# mcu.net
KiCad netlist of a schematic drawn in Altium Designer
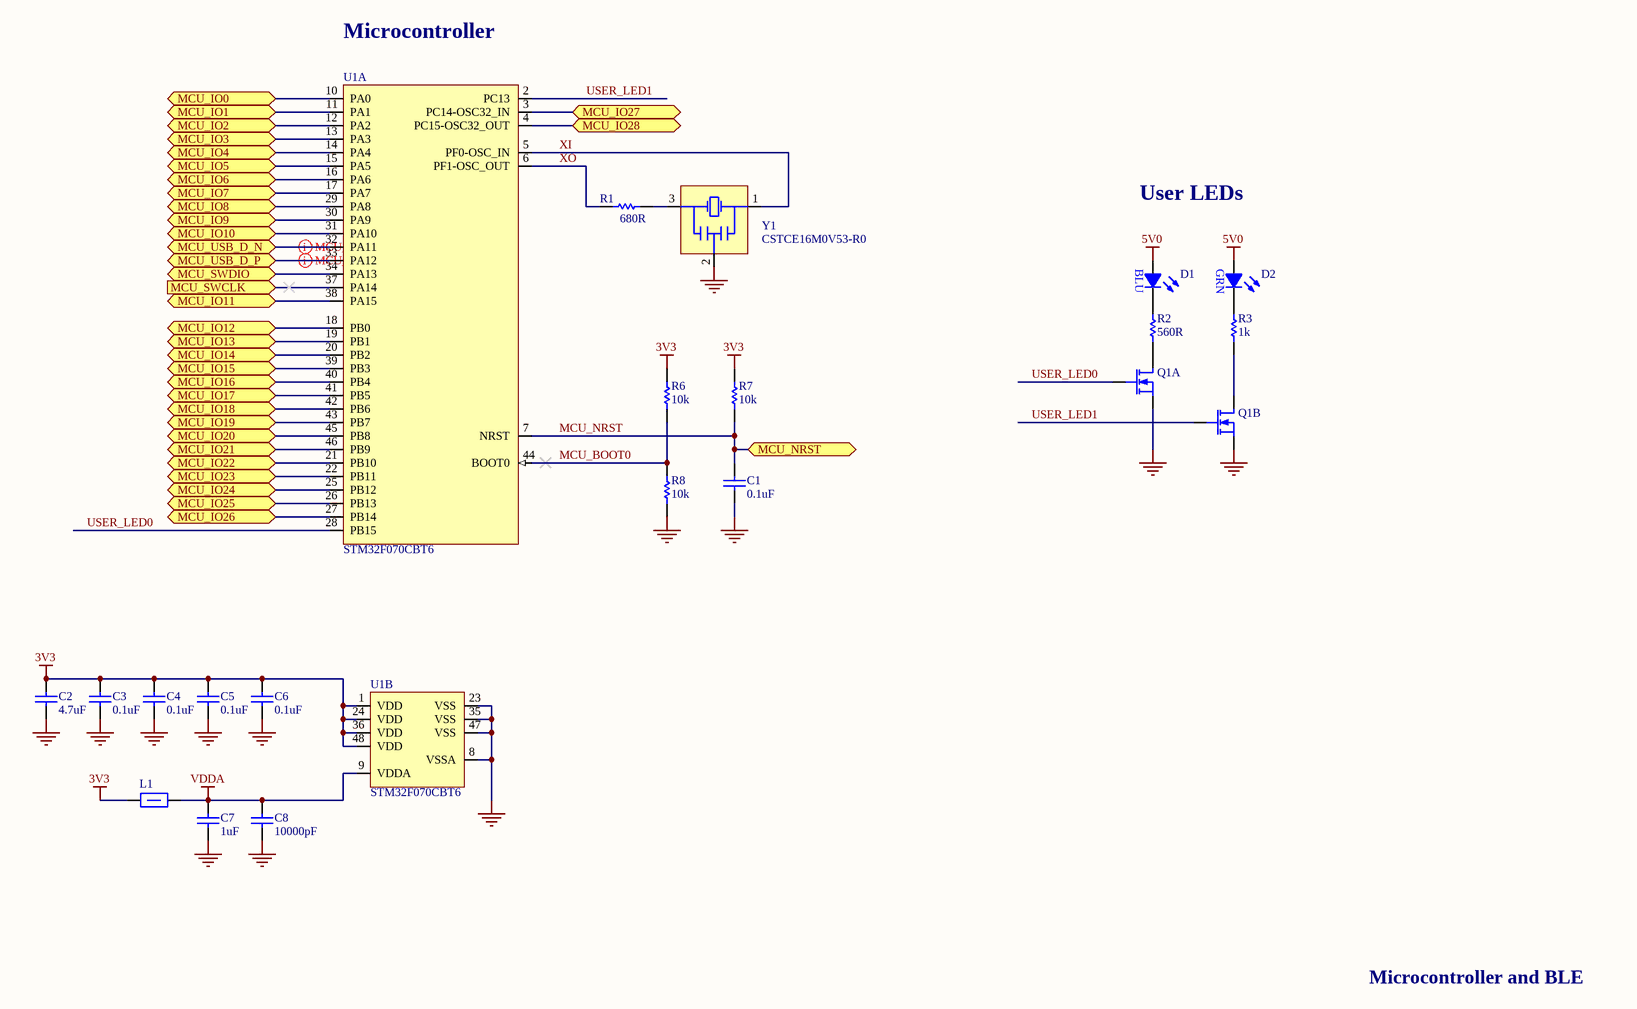
[diagram p0: mcu.SchDoc]

(export (version "E")
  (design (tool "Eeschema 10.0.6"))
  (components
    (comp (ref "C1")
      (value "0.1uF")
      (footprint "C0201")
      (description "CAP CER 0.1UF 16V X5R 0201")
      (fields
        (field (name "MANUFACTURER") "Murata")
        (field (name "MANUFACTURER PART NUMBER") "GRM033R61C104ME84D")
      )
      (libsource (lib "Capacitors") (part "0.1uF 16V 0201"))
    )
    (comp (ref "C2")
      (value "4.7uF")
      (footprint "C0402")
      (description "CAP CER 4.7UF 16V X5R 0402")
      (fields
        (field (name "MANUFACTURER") "Samsung")
        (field (name "MANUFACTURER PART NUMBER") "CL05A475MO5NUNC")
      )
      (libsource (lib "Capacitors") (part "4.7uF 16V 0402"))
    )
    (comp (ref "C3")
      (value "0.1uF")
      (footprint "C0201")
      (description "CAP CER 0.1UF 16V X5R 0201")
      (fields
        (field (name "MANUFACTURER") "Murata")
        (field (name "MANUFACTURER PART NUMBER") "GRM033R61C104ME84D")
      )
      (libsource (lib "Capacitors") (part "0.1uF 16V 0201"))
    )
    (comp (ref "C4")
      (value "0.1uF")
      (footprint "C0201")
      (description "CAP CER 0.1UF 16V X5R 0201")
      (fields
        (field (name "MANUFACTURER") "Murata")
        (field (name "MANUFACTURER PART NUMBER") "GRM033R61C104ME84D")
      )
      (libsource (lib "Capacitors") (part "0.1uF 16V 0201"))
    )
    (comp (ref "C5")
      (value "0.1uF")
      (footprint "C0201")
      (description "CAP CER 0.1UF 16V X5R 0201")
      (fields
        (field (name "MANUFACTURER") "Murata")
        (field (name "MANUFACTURER PART NUMBER") "GRM033R61C104ME84D")
      )
      (libsource (lib "Capacitors") (part "0.1uF 16V 0201"))
    )
    (comp (ref "C6")
      (value "0.1uF")
      (footprint "C0201")
      (description "CAP CER 0.1UF 16V X5R 0201")
      (fields
        (field (name "MANUFACTURER") "Murata")
        (field (name "MANUFACTURER PART NUMBER") "GRM033R61C104ME84D")
      )
      (libsource (lib "Capacitors") (part "0.1uF 16V 0201"))
    )
    (comp (ref "C7")
      (value "1uF")
      (footprint "C0402")
      (description "CAP CER 1UF 25V X5R 0402")
      (fields
        (field (name "MANUFACTURER") "Taiyo Yuden")
        (field (name "MANUFACTURER PART NUMBER") "TMK105BJ105MV-F")
      )
      (libsource (lib "Capacitors") (part "1uF 25V 0402"))
    )
    (comp (ref "C8")
      (value "10000pF")
      (footprint "C0201")
      (description "CAP CER 10000PF 25V X5R 0201")
      (fields
        (field (name "MANUFACTURER") "Murata")
        (field (name "MANUFACTURER PART NUMBER") "GRM033R61E103MA12D")
      )
      (libsource (lib "Capacitors") (part "10000pF 25V 0201"))
    )
    (comp (ref "D1")
      (value "5988091107F")
      (footprint "LED0603")
      (description "LED BLUE CLEAR 0603 SMD")
      (fields
        (field (name "MANUFACTURER") "Dialight")
        (field (name "MANUFACTURER PART NUMBER") "598-8091-107F")
      )
      (libsource (lib "Diodes") (part "Blue 0603 LED"))
    )
    (comp (ref "D2")
      (value "5988070107F")
      (footprint "LED0603")
      (description "LED GREEN CLEAR 0603 SMD")
      (fields
        (field (name "MANUFACTURER") "Dialight")
        (field (name "MANUFACTURER PART NUMBER") "598-8070-107F")
      )
      (libsource (lib "Diodes") (part "Green 0603 LED"))
    )
    (comp (ref "L1")
      (value "BLM15AG601SN1D")
      (footprint "L0402")
      (description "FERRITE BEAD 600 OHM 0402 1LN")
      (fields (field (name "MANUFACTURER") "Murata") (field (name "TOLERANCE") "25%"))
      (libsource (lib "Inductors") (part "BLM15AG601SN1D"))
    )
    (comp (ref "Q1")
      (value "PMDXB600UNE")
      (footprint "NXP_DFN1010B-6")
      (description "MOSFET 2N-CH 20V 0.6A 6DFN")
      (fields (field (name "MANUFACTURER") "NXP Semiconductors"))
      (libsource (lib "ICs") (part "PMDXB600UNE"))
    )
    (comp (ref "R1")
      (value "680R")
      (footprint "R0201")
      (description "RES SMD 680 OHM 1% 1/20W 0201")
      (fields
        (field (name "MANUFACTURER") "Yageo")
        (field (name "MANUFACTURER PART NUMBER") "RC0201FR-07680RL")
      )
      (libsource (lib "Resistors") (part "680R 0201"))
    )
    (comp (ref "R2")
      (value "560R")
      (footprint "R0201")
      (description "RES SMD 560 OHM 1% 1/20W 0201")
      (fields
        (field (name "MANUFACTURER") "Panasonic ECG")
        (field (name "MANUFACTURER PART NUMBER") "ERJ-1GEF5600C")
      )
      (libsource (lib "Resistors") (part "560R 0201"))
    )
    (comp (ref "R3")
      (value "1k")
      (footprint "R0201")
      (description "RES SMD 1K OHM 1% 1/20W 0201")
      (fields
        (field (name "MANUFACTURER") "Panasonic ECG")
        (field (name "MANUFACTURER PART NUMBER") "ERJ-1GEF1001C")
      )
      (libsource (lib "Resistors") (part "1k 0201"))
    )
    (comp (ref "R6")
      (value "10k")
      (footprint "R0201")
      (description "RES SMD 10K OHM 1% 1/20W 0201")
      (fields
        (field (name "MANUFACTURER") "Panasonic ECG")
        (field (name "MANUFACTURER PART NUMBER") "ERJ-1GEF1002C")
      )
      (libsource (lib "Resistors") (part "10k 0201"))
    )
    (comp (ref "R7")
      (value "10k")
      (footprint "R0201")
      (description "RES SMD 10K OHM 1% 1/20W 0201")
      (fields
        (field (name "MANUFACTURER") "Panasonic ECG")
        (field (name "MANUFACTURER PART NUMBER") "ERJ-1GEF1002C")
      )
      (libsource (lib "Resistors") (part "10k 0201"))
    )
    (comp (ref "R8")
      (value "10k")
      (footprint "R0201")
      (description "RES SMD 10K OHM 1% 1/20W 0201")
      (fields
        (field (name "MANUFACTURER") "Panasonic ECG")
        (field (name "MANUFACTURER PART NUMBER") "ERJ-1GEF1002C")
      )
      (libsource (lib "Resistors") (part "10k 0201"))
    )
    (comp (ref "U1")
      (value "STM32F070CBT6")
      (footprint "STM_LQFP48")
      (description "IC MCU 32BIT 128KB FLASH 48LQFP")
      (fields (field (name "MANUFACTURER") "STMicroelectronics"))
      (libsource (lib "") (part "STM32F070CBT6_1"))
    )
    (comp (ref "Y1")
      (value "CSTCE16M0V53-R0")
      (footprint "MUR_CSTCE_V")
      (description "CER RES 16.0000MHZ 15PF SMD")
      (fields (field (name "MANUFACTURER") "Murata") (field (name "TOLERANCE") "0.5%"))
      (libsource (lib "Oscillators") (part "16MHz Resonator"))
    )
  )
  (nets
    (net (code "1") (name "/MCU_BOOT0") (class "Default")
      (node (ref "R6") (pin "1") (pinfunction "1_1") (pintype "passive"))
      (node (ref "R8") (pin "2") (pinfunction "2_2") (pintype "passive"))
      (node (ref "U1") (pin "44") (pinfunction "BOOT0_44") (pintype "input"))
    )
    (net (code "2") (name "/MCU_IO0") (class "Default")
      (node (ref "U1") (pin "10") (pinfunction "PA0_10") (pintype "bidirectional"))
    )
    (net (code "3") (name "/MCU_IO1") (class "Default")
      (node (ref "U1") (pin "11") (pinfunction "PA1_11") (pintype "bidirectional"))
    )
    (net (code "4") (name "/MCU_IO2") (class "Default")
      (node (ref "U1") (pin "12") (pinfunction "PA2_12") (pintype "bidirectional"))
    )
    (net (code "5") (name "/MCU_IO3") (class "Default")
      (node (ref "U1") (pin "13") (pinfunction "PA3_13") (pintype "bidirectional"))
    )
    (net (code "6") (name "/MCU_IO4") (class "Default")
      (node (ref "U1") (pin "14") (pinfunction "PA4_14") (pintype "bidirectional"))
    )
    (net (code "7") (name "/MCU_IO5") (class "Default")
      (node (ref "U1") (pin "15") (pinfunction "PA5_15") (pintype "bidirectional"))
    )
    (net (code "8") (name "/MCU_IO6") (class "Default")
      (node (ref "U1") (pin "16") (pinfunction "PA6_16") (pintype "bidirectional"))
    )
    (net (code "9") (name "/MCU_IO7") (class "Default")
      (node (ref "U1") (pin "17") (pinfunction "PA7_17") (pintype "bidirectional"))
    )
    (net (code "10") (name "/MCU_IO8") (class "Default")
      (node (ref "U1") (pin "29") (pinfunction "PA8_29") (pintype "bidirectional"))
    )
    (net (code "11") (name "/MCU_IO9") (class "Default")
      (node (ref "U1") (pin "30") (pinfunction "PA9_30") (pintype "bidirectional"))
    )
    (net (code "12") (name "/MCU_IO10") (class "Default")
      (node (ref "U1") (pin "31") (pinfunction "PA10_31") (pintype "bidirectional"))
    )
    (net (code "13") (name "/MCU_IO11") (class "Default")
      (node (ref "U1") (pin "38") (pinfunction "PA15_38") (pintype "bidirectional"))
    )
    (net (code "14") (name "/MCU_IO12") (class "Default")
      (node (ref "U1") (pin "18") (pinfunction "PB0_18") (pintype "bidirectional"))
    )
    (net (code "15") (name "/MCU_IO13") (class "Default")
      (node (ref "U1") (pin "19") (pinfunction "PB1_19") (pintype "bidirectional"))
    )
    (net (code "16") (name "/MCU_IO14") (class "Default")
      (node (ref "U1") (pin "20") (pinfunction "PB2_20") (pintype "bidirectional"))
    )
    (net (code "17") (name "/MCU_IO15") (class "Default")
      (node (ref "U1") (pin "39") (pinfunction "PB3_39") (pintype "bidirectional"))
    )
    (net (code "18") (name "/MCU_IO16") (class "Default")
      (node (ref "U1") (pin "40") (pinfunction "PB4_40") (pintype "bidirectional"))
    )
    (net (code "19") (name "/MCU_IO17") (class "Default")
      (node (ref "U1") (pin "41") (pinfunction "PB5_41") (pintype "bidirectional"))
    )
    (net (code "20") (name "/MCU_IO18") (class "Default")
      (node (ref "U1") (pin "42") (pinfunction "PB6_42") (pintype "bidirectional"))
    )
    (net (code "21") (name "/MCU_IO19") (class "Default")
      (node (ref "U1") (pin "43") (pinfunction "PB7_43") (pintype "bidirectional"))
    )
    (net (code "22") (name "/MCU_IO20") (class "Default")
      (node (ref "U1") (pin "45") (pinfunction "PB8_45") (pintype "bidirectional"))
    )
    (net (code "23") (name "/MCU_IO21") (class "Default")
      (node (ref "U1") (pin "46") (pinfunction "PB9_46") (pintype "bidirectional"))
    )
    (net (code "24") (name "/MCU_IO22") (class "Default")
      (node (ref "U1") (pin "21") (pinfunction "PB10_21") (pintype "bidirectional"))
    )
    (net (code "25") (name "/MCU_IO23") (class "Default")
      (node (ref "U1") (pin "22") (pinfunction "PB11_22") (pintype "bidirectional"))
    )
    (net (code "26") (name "/MCU_IO24") (class "Default")
      (node (ref "U1") (pin "25") (pinfunction "PB12_25") (pintype "bidirectional"))
    )
    (net (code "27") (name "/MCU_IO25") (class "Default")
      (node (ref "U1") (pin "26") (pinfunction "PB13_26") (pintype "bidirectional"))
    )
    (net (code "28") (name "/MCU_IO26") (class "Default")
      (node (ref "U1") (pin "27") (pinfunction "PB14_27") (pintype "bidirectional"))
    )
    (net (code "29") (name "/MCU_IO27") (class "Default")
      (node (ref "U1") (pin "3") (pinfunction "PC14-OSC32_IN_3") (pintype "bidirectional"))
    )
    (net (code "30") (name "/MCU_IO28") (class "Default")
      (node (ref "U1") (pin "4") (pinfunction "PC15-OSC32_OUT_4") (pintype "bidirectional"))
    )
    (net (code "31") (name "/MCU_NRST") (class "Default")
      (node (ref "C1") (pin "2") (pinfunction "2_2") (pintype "passive"))
      (node (ref "R7") (pin "1") (pinfunction "1_1") (pintype "passive"))
      (node (ref "U1") (pin "7") (pinfunction "NRST_7") (pintype "bidirectional"))
    )
    (net (code "32") (name "/MCU_SWCLK") (class "Default")
      (node (ref "U1") (pin "37") (pinfunction "PA14_37") (pintype "bidirectional"))
    )
    (net (code "33") (name "/MCU_SWDIO") (class "Default")
      (node (ref "U1") (pin "34") (pinfunction "PA13_34") (pintype "bidirectional"))
    )
    (net (code "34") (name "/MCU_USB_D_N") (class "Default")
      (node (ref "U1") (pin "32") (pinfunction "PA11_32") (pintype "bidirectional"))
    )
    (net (code "35") (name "/MCU_USB_D_P") (class "Default")
      (node (ref "U1") (pin "33") (pinfunction "PA12_33") (pintype "bidirectional"))
    )
    (net (code "36") (name "/USER_LED0") (class "Default")
      (node (ref "Q1") (pin "2") (pinfunction "G1_2") (pintype "passive"))
      (node (ref "U1") (pin "28") (pinfunction "PB15_28") (pintype "bidirectional"))
    )
    (net (code "37") (name "/USER_LED1") (class "Default")
      (node (ref "Q1") (pin "5") (pinfunction "G2_5") (pintype "passive"))
      (node (ref "U1") (pin "2") (pinfunction "PC13_2") (pintype "bidirectional"))
    )
    (net (code "38") (name "/XI") (class "Default")
      (node (ref "U1") (pin "5") (pinfunction "PF0-OSC_IN_5") (pintype "bidirectional"))
      (node (ref "Y1") (pin "1") (pinfunction "1_1") (pintype "passive"))
    )
    (net (code "39") (name "/XO") (class "Default")
      (node (ref "R1") (pin "1") (pinfunction "1_1") (pintype "passive"))
      (node (ref "U1") (pin "6") (pinfunction "PF1-OSC_OUT_6") (pintype "bidirectional"))
    )
    (net (code "40") (name "3V3") (class "Default")
      (node (ref "C2") (pin "2") (pinfunction "2_2") (pintype "passive"))
      (node (ref "C3") (pin "2") (pinfunction "2_2") (pintype "passive"))
      (node (ref "C4") (pin "2") (pinfunction "2_2") (pintype "passive"))
      (node (ref "C5") (pin "2") (pinfunction "2_2") (pintype "passive"))
      (node (ref "C6") (pin "2") (pinfunction "2_2") (pintype "passive"))
      (node (ref "L1") (pin "1") (pinfunction "1_1") (pintype "passive"))
      (node (ref "R6") (pin "2") (pinfunction "2_2") (pintype "passive"))
      (node (ref "R7") (pin "2") (pinfunction "2_2") (pintype "passive"))
      (node (ref "U1") (pin "1") (pinfunction "VDD_1") (pintype "power_in"))
      (node (ref "U1") (pin "24") (pinfunction "VDD_24") (pintype "power_in"))
      (node (ref "U1") (pin "36") (pinfunction "VDD_36") (pintype "power_in"))
      (node (ref "U1") (pin "48") (pinfunction "VDD_48") (pintype "power_in"))
    )
    (net (code "41") (name "5V0") (class "Default")
      (node (ref "D1") (pin "2") (pinfunction "A_2") (pintype "passive"))
      (node (ref "D2") (pin "2") (pinfunction "A_2") (pintype "passive"))
    )
    (net (code "42") (name "GND") (class "Default")
      (node (ref "C1") (pin "1") (pinfunction "1_1") (pintype "passive"))
      (node (ref "C2") (pin "1") (pinfunction "1_1") (pintype "passive"))
      (node (ref "C3") (pin "1") (pinfunction "1_1") (pintype "passive"))
      (node (ref "C4") (pin "1") (pinfunction "1_1") (pintype "passive"))
      (node (ref "C5") (pin "1") (pinfunction "1_1") (pintype "passive"))
      (node (ref "C6") (pin "1") (pinfunction "1_1") (pintype "passive"))
      (node (ref "C7") (pin "1") (pinfunction "1_1") (pintype "passive"))
      (node (ref "C8") (pin "1") (pinfunction "1_1") (pintype "passive"))
      (node (ref "Q1") (pin "1") (pinfunction "S1_1") (pintype "passive"))
      (node (ref "Q1") (pin "4") (pinfunction "S2_4") (pintype "passive"))
      (node (ref "R8") (pin "1") (pinfunction "1_1") (pintype "passive"))
      (node (ref "U1") (pin "23") (pinfunction "VSS_23") (pintype "power_in"))
      (node (ref "U1") (pin "35") (pinfunction "VSS_35") (pintype "power_in"))
      (node (ref "U1") (pin "47") (pinfunction "VSS_47") (pintype "power_in"))
      (node (ref "U1") (pin "8") (pinfunction "VSSA_8") (pintype "power_in"))
      (node (ref "Y1") (pin "2") (pinfunction "2_2") (pintype "passive"))
    )
    (net (code "43") (name "Net-(D1-K)") (class "Default")
      (node (ref "D1") (pin "1") (pinfunction "K_1") (pintype "passive"))
      (node (ref "R2") (pin "2") (pinfunction "2_2") (pintype "passive"))
    )
    (net (code "44") (name "Net-(D2-K)") (class "Default")
      (node (ref "D2") (pin "1") (pinfunction "K_1") (pintype "passive"))
      (node (ref "R3") (pin "2") (pinfunction "2_2") (pintype "passive"))
    )
    (net (code "45") (name "Net-(Q1A-D1)") (class "Default")
      (node (ref "Q1") (pin "6") (pinfunction "D1_6") (pintype "passive"))
      (node (ref "R2") (pin "1") (pinfunction "1_1") (pintype "passive"))
    )
    (net (code "46") (name "Net-(Q1B-S2-Pad3)") (class "Default")
      (node (ref "Q1") (pin "3") (pinfunction "S2_3") (pintype "passive"))
      (node (ref "R3") (pin "1") (pinfunction "1_1") (pintype "passive"))
    )
    (net (code "47") (name "Net-(R1-Pad2)") (class "Default")
      (node (ref "R1") (pin "2") (pinfunction "2_2") (pintype "passive"))
      (node (ref "Y1") (pin "3") (pinfunction "3_3") (pintype "passive"))
    )
    (net (code "48") (name "VDDA") (class "Default")
      (node (ref "C7") (pin "2") (pinfunction "2_2") (pintype "passive"))
      (node (ref "C8") (pin "2") (pinfunction "2_2") (pintype "passive"))
      (node (ref "L1") (pin "2") (pinfunction "2_2") (pintype "passive"))
      (node (ref "U1") (pin "9") (pinfunction "VDDA_9") (pintype "power_in"))
    )
  )
)
